# Relays.net
KiCad netlist of a schematic drawn in Altium Designer
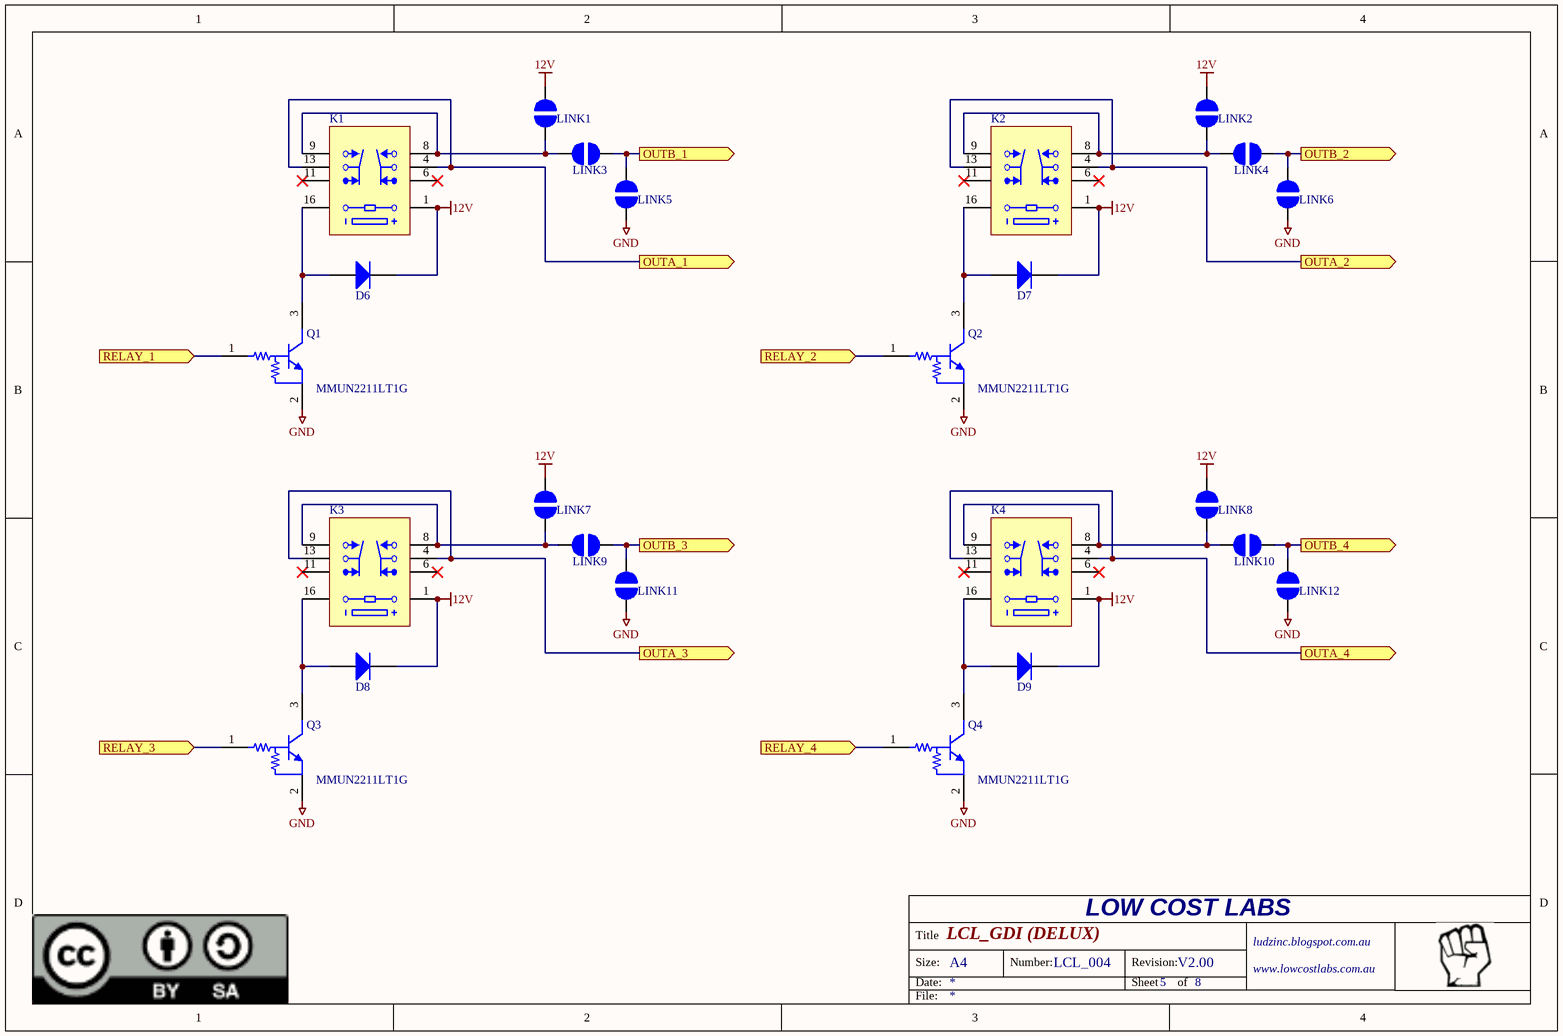
[diagram p0: Relays.SchDoc]

(export (version "E")
  (design (tool "Eeschema 10.0.6"))
  (components
    (comp (ref "D6")
      (value "Vishay / Semiconductors S1MHE3/61T")
      (footprint "ONSC-SMA-2-403D-02_V")
      (description "DIODE GPP 1A 1000V SMA DO-214AC")
      (fields (field (name "MANUFACTURER PART NUMBER") "S1MHE3/61T") (field (name "MANUFACTURER") "Vishay"))
      (libsource (lib "FavoritesLibrary") (part "DIOD-D-A1K2-2"))
    )
    (comp (ref "D7")
      (value "Vishay / Semiconductors S1MHE3/61T")
      (footprint "ONSC-SMA-2-403D-02_V")
      (description "DIODE GPP 1A 1000V SMA DO-214AC")
      (fields (field (name "MANUFACTURER PART NUMBER") "S1MHE3/61T") (field (name "MANUFACTURER") "Vishay"))
      (libsource (lib "FavoritesLibrary") (part "DIOD-D-A1K2-2"))
    )
    (comp (ref "D8")
      (value "Vishay / Semiconductors S1MHE3/61T")
      (footprint "ONSC-SMA-2-403D-02_V")
      (description "DIODE GPP 1A 1000V SMA DO-214AC")
      (fields (field (name "MANUFACTURER PART NUMBER") "S1MHE3/61T") (field (name "MANUFACTURER") "Vishay"))
      (libsource (lib "FavoritesLibrary") (part "DIOD-D-A1K2-2"))
    )
    (comp (ref "D9")
      (value "Vishay / Semiconductors S1MHE3/61T")
      (footprint "ONSC-SMA-2-403D-02_V")
      (description "DIODE GPP 1A 1000V SMA DO-214AC")
      (fields (field (name "MANUFACTURER PART NUMBER") "S1MHE3/61T") (field (name "MANUFACTURER") "Vishay"))
      (libsource (lib "FavoritesLibrary") (part "DIOD-D-A1K2-2"))
    )
    (comp (ref "K1")
      (value "Panasonic DS2Y-S-DC12V")
      (footprint "PCB-d08qloczi00j7cf9smyl-1")
      (description "Relay; E-Mech; non-Latching; DPDT-NO/NC; Cur-Rtg 2A; Ctrl-V 12DC; Vol-Rtg 250/220AC/DC")
      (fields (field (name "MANUFACTURER PART NUMBER") "DS2Y-S-DC12V"))
      (libsource (lib "CommunityVault") (part "PNSC-TQ2SA-10"))
    )
    (comp (ref "K2")
      (value "Panasonic DS2Y-S-DC12V")
      (footprint "PCB-d08qloczi00j7cf9smyl-1")
      (description "Relay; E-Mech; non-Latching; DPDT-NO/NC; Cur-Rtg 2A; Ctrl-V 12DC; Vol-Rtg 250/220AC/DC")
      (fields (field (name "MANUFACTURER PART NUMBER") "DS2Y-S-DC12V"))
      (libsource (lib "CommunityVault") (part "PNSC-TQ2SA-10"))
    )
    (comp (ref "K3")
      (value "Panasonic DS2Y-S-DC12V")
      (footprint "PCB-d08qloczi00j7cf9smyl-1")
      (description "Relay; E-Mech; non-Latching; DPDT-NO/NC; Cur-Rtg 2A; Ctrl-V 12DC; Vol-Rtg 250/220AC/DC")
      (fields (field (name "MANUFACTURER PART NUMBER") "DS2Y-S-DC12V"))
      (libsource (lib "CommunityVault") (part "PNSC-TQ2SA-10"))
    )
    (comp (ref "K4")
      (value "Panasonic DS2Y-S-DC12V")
      (footprint "PCB-d08qloczi00j7cf9smyl-1")
      (description "Relay; E-Mech; non-Latching; DPDT-NO/NC; Cur-Rtg 2A; Ctrl-V 12DC; Vol-Rtg 250/220AC/DC")
      (fields (field (name "MANUFACTURER PART NUMBER") "DS2Y-S-DC12V"))
      (libsource (lib "CommunityVault") (part "PNSC-TQ2SA-10"))
    )
    (comp (ref "LINK1")
      (value "SOLDER JUMPER")
      (footprint "PCB-btzmmfon80v3o3bq8yuz-1")
      (libsource (lib "FavoritesLibrary") (part "SYM-awopsk420h7r935fi2ee-1"))
    )
    (comp (ref "LINK2")
      (value "SOLDER JUMPER")
      (footprint "PCB-btzmmfon80v3o3bq8yuz-1")
      (libsource (lib "FavoritesLibrary") (part "SYM-awopsk420h7r935fi2ee-1"))
    )
    (comp (ref "LINK3")
      (value "SOLDER JUMPER")
      (footprint "PCB-btzmmfon80v3o3bq8yuz-1")
      (libsource (lib "FavoritesLibrary") (part "SYM-awopsk420h7r935fi2ee-1"))
    )
    (comp (ref "LINK4")
      (value "SOLDER JUMPER")
      (footprint "PCB-btzmmfon80v3o3bq8yuz-1")
      (libsource (lib "FavoritesLibrary") (part "SYM-awopsk420h7r935fi2ee-1"))
    )
    (comp (ref "LINK5")
      (value "SOLDER JUMPER")
      (footprint "PCB-btzmmfon80v3o3bq8yuz-1")
      (libsource (lib "FavoritesLibrary") (part "SYM-awopsk420h7r935fi2ee-1"))
    )
    (comp (ref "LINK6")
      (value "SOLDER JUMPER")
      (footprint "PCB-btzmmfon80v3o3bq8yuz-1")
      (libsource (lib "FavoritesLibrary") (part "SYM-awopsk420h7r935fi2ee-1"))
    )
    (comp (ref "LINK7")
      (value "SOLDER JUMPER")
      (footprint "PCB-btzmmfon80v3o3bq8yuz-1")
      (libsource (lib "FavoritesLibrary") (part "SYM-awopsk420h7r935fi2ee-1"))
    )
    (comp (ref "LINK8")
      (value "SOLDER JUMPER")
      (footprint "PCB-btzmmfon80v3o3bq8yuz-1")
      (libsource (lib "FavoritesLibrary") (part "SYM-awopsk420h7r935fi2ee-1"))
    )
    (comp (ref "LINK9")
      (value "SOLDER JUMPER")
      (footprint "PCB-btzmmfon80v3o3bq8yuz-1")
      (libsource (lib "FavoritesLibrary") (part "SYM-awopsk420h7r935fi2ee-1"))
    )
    (comp (ref "LINK10")
      (value "SOLDER JUMPER")
      (footprint "PCB-btzmmfon80v3o3bq8yuz-1")
      (libsource (lib "FavoritesLibrary") (part "SYM-awopsk420h7r935fi2ee-1"))
    )
    (comp (ref "LINK11")
      (value "SOLDER JUMPER")
      (footprint "PCB-btzmmfon80v3o3bq8yuz-1")
      (libsource (lib "FavoritesLibrary") (part "SYM-awopsk420h7r935fi2ee-1"))
    )
    (comp (ref "LINK12")
      (value "SOLDER JUMPER")
      (footprint "PCB-btzmmfon80v3o3bq8yuz-1")
      (libsource (lib "FavoritesLibrary") (part "SYM-awopsk420h7r935fi2ee-1"))
    )
    (comp (ref "Q1")
      (value "MMUN2211LT1G")
      (footprint "ONSC-SOT-23-3-318-08_V")
      (libsource (lib "CommunityVault") (part "ONSC-BRT-NPN-B1E2C3-3"))
    )
    (comp (ref "Q2")
      (value "MMUN2211LT1G")
      (footprint "ONSC-SOT-23-3-318-08_V")
      (libsource (lib "CommunityVault") (part "ONSC-BRT-NPN-B1E2C3-3"))
    )
    (comp (ref "Q3")
      (value "MMUN2211LT1G")
      (footprint "ONSC-SOT-23-3-318-08_V")
      (libsource (lib "CommunityVault") (part "ONSC-BRT-NPN-B1E2C3-3"))
    )
    (comp (ref "Q4")
      (value "MMUN2211LT1G")
      (footprint "ONSC-SOT-23-3-318-08_V")
      (libsource (lib "CommunityVault") (part "ONSC-BRT-NPN-B1E2C3-3"))
    )
  )
  (nets
    (net (code "1") (name "/OUTA_1") (class "Default")
      (node (ref "K1") (pin "13") (pinfunction "13_13") (pintype "passive"))
      (node (ref "K1") (pin "4") (pinfunction "4_4") (pintype "passive"))
    )
    (net (code "2") (name "/OUTA_2") (class "Default")
      (node (ref "K2") (pin "13") (pinfunction "13_13") (pintype "passive"))
      (node (ref "K2") (pin "4") (pinfunction "4_4") (pintype "passive"))
    )
    (net (code "3") (name "/OUTA_3") (class "Default")
      (node (ref "K3") (pin "13") (pinfunction "13_13") (pintype "passive"))
      (node (ref "K3") (pin "4") (pinfunction "4_4") (pintype "passive"))
    )
    (net (code "4") (name "/OUTA_4") (class "Default")
      (node (ref "K4") (pin "13") (pinfunction "13_13") (pintype "passive"))
      (node (ref "K4") (pin "4") (pinfunction "4_4") (pintype "passive"))
    )
    (net (code "5") (name "/OUTB_1") (class "Default")
      (node (ref "LINK3") (pin "2") (pinfunction "2_2") (pintype "passive"))
      (node (ref "LINK5") (pin "1") (pinfunction "1_1") (pintype "passive"))
    )
    (net (code "6") (name "/OUTB_2") (class "Default")
      (node (ref "LINK4") (pin "2") (pinfunction "2_2") (pintype "passive"))
      (node (ref "LINK6") (pin "1") (pinfunction "1_1") (pintype "passive"))
    )
    (net (code "7") (name "/OUTB_3") (class "Default")
      (node (ref "LINK11") (pin "1") (pinfunction "1_1") (pintype "passive"))
      (node (ref "LINK9") (pin "2") (pinfunction "2_2") (pintype "passive"))
    )
    (net (code "8") (name "/OUTB_4") (class "Default")
      (node (ref "LINK10") (pin "2") (pinfunction "2_2") (pintype "passive"))
      (node (ref "LINK12") (pin "1") (pinfunction "1_1") (pintype "passive"))
    )
    (net (code "9") (name "/RELAY_1") (class "Default")
      (node (ref "Q1") (pin "1") (pinfunction "B_1") (pintype "passive"))
    )
    (net (code "10") (name "/RELAY_2") (class "Default")
      (node (ref "Q2") (pin "1") (pinfunction "B_1") (pintype "passive"))
    )
    (net (code "11") (name "/RELAY_3") (class "Default")
      (node (ref "Q3") (pin "1") (pinfunction "B_1") (pintype "passive"))
    )
    (net (code "12") (name "/RELAY_4") (class "Default")
      (node (ref "Q4") (pin "1") (pinfunction "B_1") (pintype "passive"))
    )
    (net (code "13") (name "12V") (class "Default")
      (node (ref "D6") (pin "2") (pinfunction "K_2") (pintype "passive"))
      (node (ref "D7") (pin "2") (pinfunction "K_2") (pintype "passive"))
      (node (ref "D8") (pin "2") (pinfunction "K_2") (pintype "passive"))
      (node (ref "D9") (pin "2") (pinfunction "K_2") (pintype "passive"))
      (node (ref "K1") (pin "1") (pinfunction "1_1") (pintype "passive"))
      (node (ref "K2") (pin "1") (pinfunction "1_1") (pintype "passive"))
      (node (ref "K3") (pin "1") (pinfunction "1_1") (pintype "passive"))
      (node (ref "K4") (pin "1") (pinfunction "1_1") (pintype "passive"))
      (node (ref "LINK1") (pin "1") (pinfunction "1_1") (pintype "passive"))
      (node (ref "LINK2") (pin "1") (pinfunction "1_1") (pintype "passive"))
      (node (ref "LINK7") (pin "1") (pinfunction "1_1") (pintype "passive"))
      (node (ref "LINK8") (pin "1") (pinfunction "1_1") (pintype "passive"))
    )
    (net (code "14") (name "GND") (class "Default")
      (node (ref "LINK11") (pin "2") (pinfunction "2_2") (pintype "passive"))
      (node (ref "LINK12") (pin "2") (pinfunction "2_2") (pintype "passive"))
      (node (ref "LINK5") (pin "2") (pinfunction "2_2") (pintype "passive"))
      (node (ref "LINK6") (pin "2") (pinfunction "2_2") (pintype "passive"))
      (node (ref "Q1") (pin "2") (pinfunction "E_2") (pintype "passive"))
      (node (ref "Q2") (pin "2") (pinfunction "E_2") (pintype "passive"))
      (node (ref "Q3") (pin "2") (pinfunction "E_2") (pintype "passive"))
      (node (ref "Q4") (pin "2") (pinfunction "E_2") (pintype "passive"))
    )
    (net (code "15") (name "Net-(D6-A)") (class "Default")
      (node (ref "D6") (pin "1") (pinfunction "A_1") (pintype "passive"))
      (node (ref "K1") (pin "16") (pinfunction "16_16") (pintype "passive"))
      (node (ref "Q1") (pin "3") (pinfunction "C_3") (pintype "passive"))
    )
    (net (code "16") (name "Net-(D7-A)") (class "Default")
      (node (ref "D7") (pin "1") (pinfunction "A_1") (pintype "passive"))
      (node (ref "K2") (pin "16") (pinfunction "16_16") (pintype "passive"))
      (node (ref "Q2") (pin "3") (pinfunction "C_3") (pintype "passive"))
    )
    (net (code "17") (name "Net-(D8-A)") (class "Default")
      (node (ref "D8") (pin "1") (pinfunction "A_1") (pintype "passive"))
      (node (ref "K3") (pin "16") (pinfunction "16_16") (pintype "passive"))
      (node (ref "Q3") (pin "3") (pinfunction "C_3") (pintype "passive"))
    )
    (net (code "18") (name "Net-(D9-A)") (class "Default")
      (node (ref "D9") (pin "1") (pinfunction "A_1") (pintype "passive"))
      (node (ref "K4") (pin "16") (pinfunction "16_16") (pintype "passive"))
      (node (ref "Q4") (pin "3") (pinfunction "C_3") (pintype "passive"))
    )
    (net (code "19") (name "Net-(K1-Pad8)") (class "Default")
      (node (ref "K1") (pin "8") (pinfunction "8_8") (pintype "passive"))
      (node (ref "K1") (pin "9") (pinfunction "9_9") (pintype "passive"))
      (node (ref "LINK1") (pin "2") (pinfunction "2_2") (pintype "passive"))
      (node (ref "LINK3") (pin "1") (pinfunction "1_1") (pintype "passive"))
    )
    (net (code "20") (name "Net-(K2-Pad8)") (class "Default")
      (node (ref "K2") (pin "8") (pinfunction "8_8") (pintype "passive"))
      (node (ref "K2") (pin "9") (pinfunction "9_9") (pintype "passive"))
      (node (ref "LINK2") (pin "2") (pinfunction "2_2") (pintype "passive"))
      (node (ref "LINK4") (pin "1") (pinfunction "1_1") (pintype "passive"))
    )
    (net (code "21") (name "Net-(K3-Pad8)") (class "Default")
      (node (ref "K3") (pin "8") (pinfunction "8_8") (pintype "passive"))
      (node (ref "K3") (pin "9") (pinfunction "9_9") (pintype "passive"))
      (node (ref "LINK7") (pin "2") (pinfunction "2_2") (pintype "passive"))
      (node (ref "LINK9") (pin "1") (pinfunction "1_1") (pintype "passive"))
    )
    (net (code "22") (name "Net-(K4-Pad8)") (class "Default")
      (node (ref "K4") (pin "8") (pinfunction "8_8") (pintype "passive"))
      (node (ref "K4") (pin "9") (pinfunction "9_9") (pintype "passive"))
      (node (ref "LINK10") (pin "1") (pinfunction "1_1") (pintype "passive"))
      (node (ref "LINK8") (pin "2") (pinfunction "2_2") (pintype "passive"))
    )
    (net (code "23") (name "unconnected-(K1-Pad6)") (class "Default")
      (node (ref "K1") (pin "6") (pinfunction "6_6") (pintype "passive+no_connect"))
    )
    (net (code "24") (name "unconnected-(K1-Pad11)") (class "Default")
      (node (ref "K1") (pin "11") (pinfunction "11_11") (pintype "passive+no_connect"))
    )
    (net (code "25") (name "unconnected-(K2-Pad6)") (class "Default")
      (node (ref "K2") (pin "6") (pinfunction "6_6") (pintype "passive+no_connect"))
    )
    (net (code "26") (name "unconnected-(K2-Pad11)") (class "Default")
      (node (ref "K2") (pin "11") (pinfunction "11_11") (pintype "passive+no_connect"))
    )
    (net (code "27") (name "unconnected-(K3-Pad6)") (class "Default")
      (node (ref "K3") (pin "6") (pinfunction "6_6") (pintype "passive+no_connect"))
    )
    (net (code "28") (name "unconnected-(K3-Pad11)") (class "Default")
      (node (ref "K3") (pin "11") (pinfunction "11_11") (pintype "passive+no_connect"))
    )
    (net (code "29") (name "unconnected-(K4-Pad6)") (class "Default")
      (node (ref "K4") (pin "6") (pinfunction "6_6") (pintype "passive+no_connect"))
    )
    (net (code "30") (name "unconnected-(K4-Pad11)") (class "Default")
      (node (ref "K4") (pin "11") (pinfunction "11_11") (pintype "passive+no_connect"))
    )
  )
)
